# 457_I2S_Stereo_Sound_Speaker_Rev020001.net
KiCad netlist of a schematic drawn in EAGLE
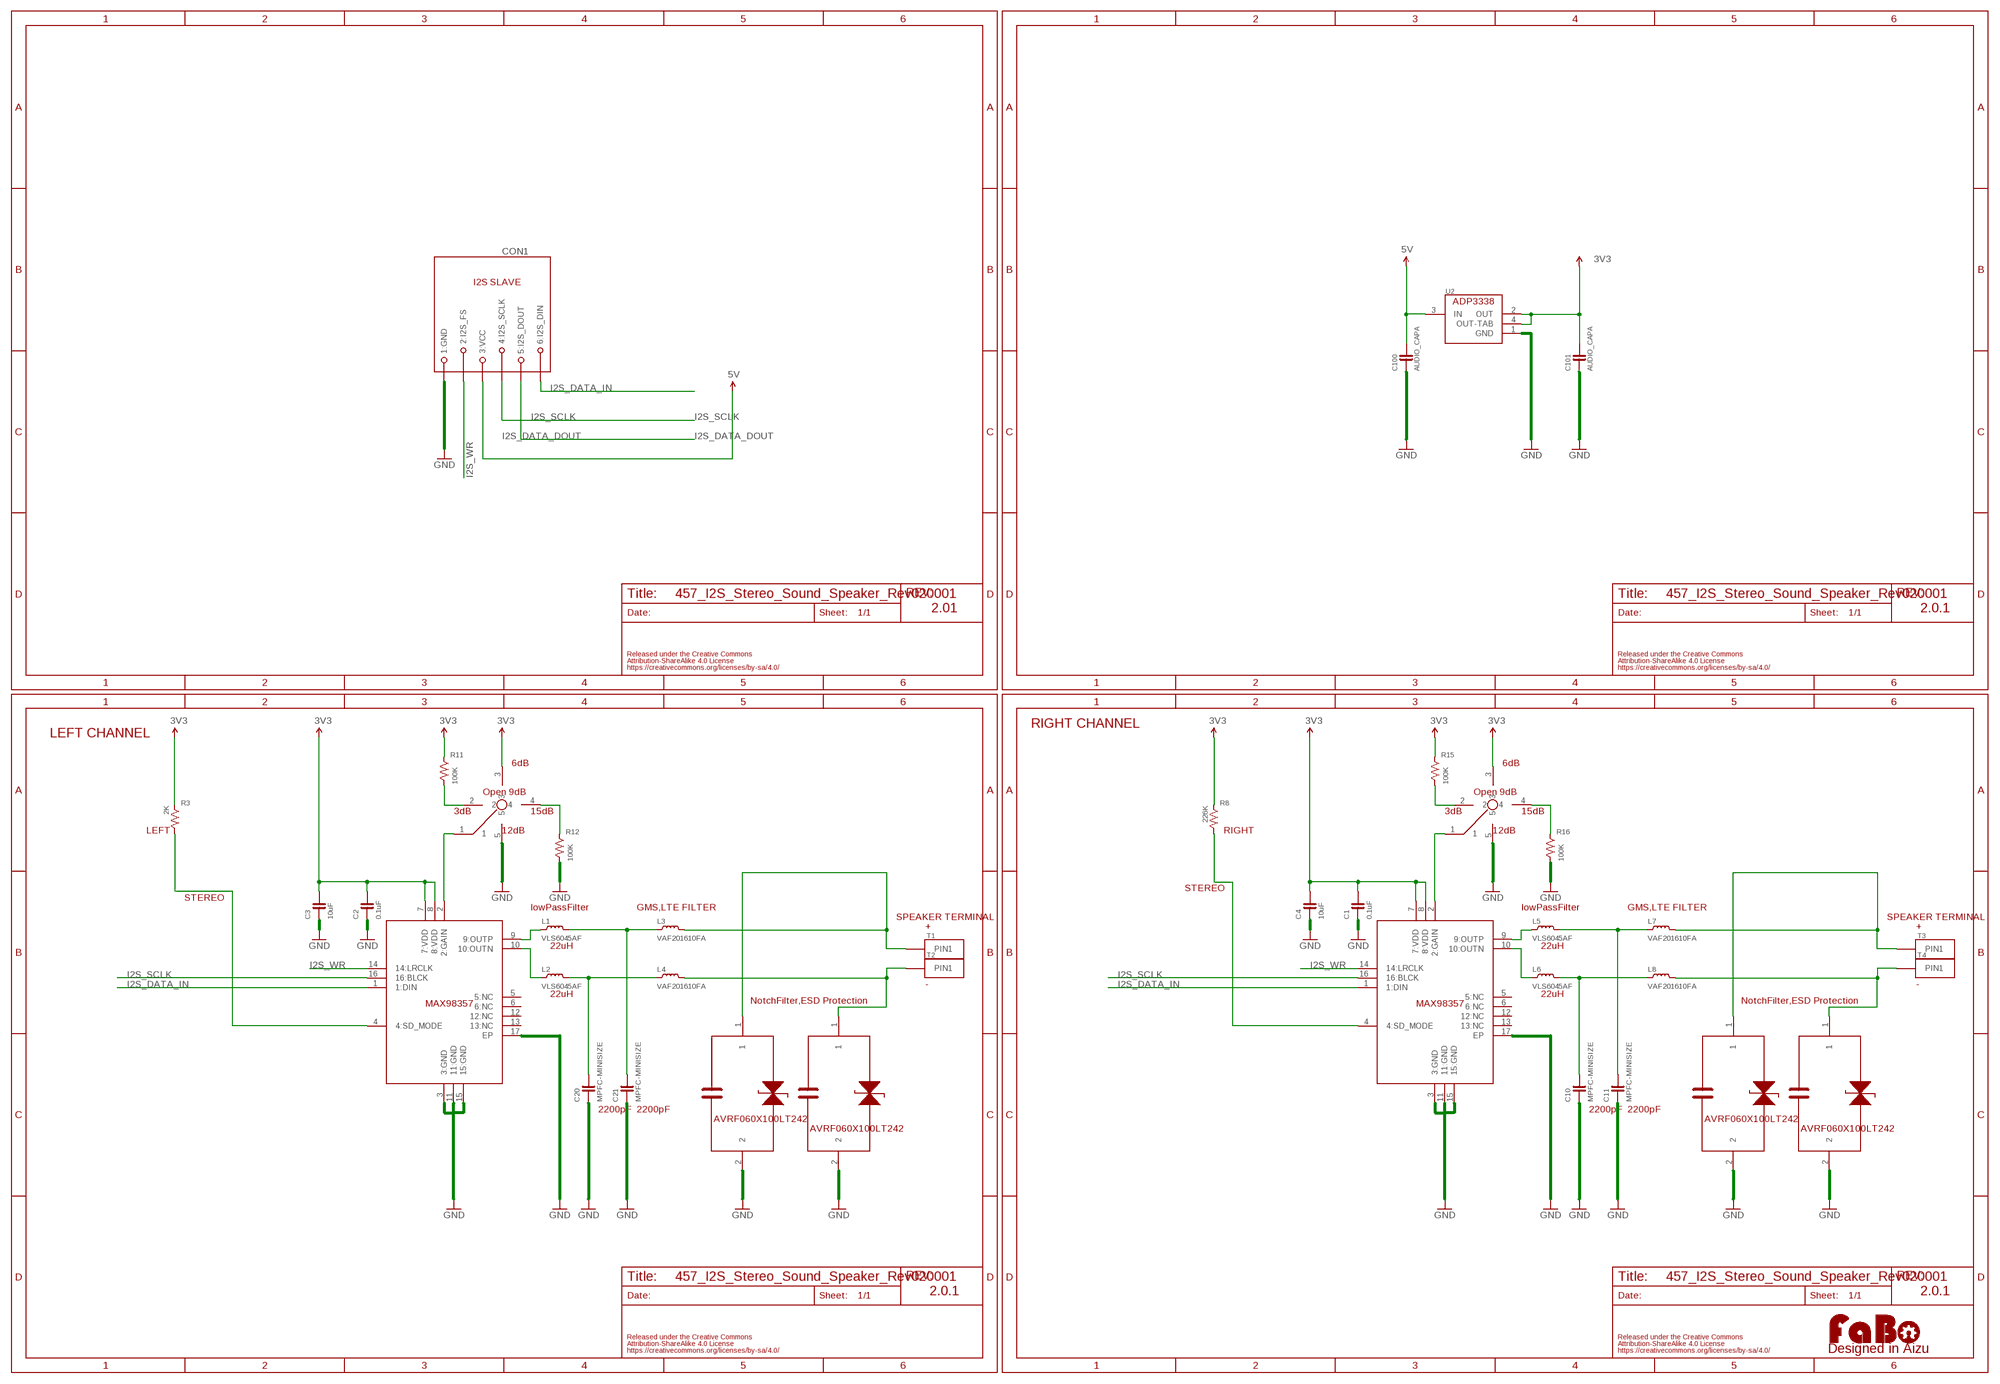
[diagram p0: schematic, sheet 1]

(export (version "E")
  (design (tool "Eeschema 10.0.6"))
  (components
    (comp (ref "C1")
      (value "0.1uF")
      (footprint "eagle-import:0603")
      (libsource (lib "eagle-import") (part "CAPACITOR-0603"))
    )
    (comp (ref "C2")
      (value "0.1uF")
      (footprint "eagle-import:0603")
      (libsource (lib "eagle-import") (part "CAPACITOR-0603"))
    )
    (comp (ref "C3")
      (value "10uF")
      (footprint "eagle-import:0603")
      (libsource (lib "eagle-import") (part "CAPACITOR-0603"))
    )
    (comp (ref "C4")
      (value "10uF")
      (footprint "eagle-import:0603")
      (libsource (lib "eagle-import") (part "CAPACITOR-0603"))
    )
    (comp (ref "C10")
      (value "MPFC-MINISIZE")
      (footprint "eagle-import:DIP-MPFC")
      (libsource (lib "eagle-import") (part "MPFC-MINISIZE"))
    )
    (comp (ref "C11")
      (value "MPFC-MINISIZE")
      (footprint "eagle-import:DIP-MPFC")
      (libsource (lib "eagle-import") (part "MPFC-MINISIZE"))
    )
    (comp (ref "C20")
      (value "MPFC-MINISIZE")
      (footprint "eagle-import:DIP-MPFC")
      (libsource (lib "eagle-import") (part "MPFC-MINISIZE"))
    )
    (comp (ref "C21")
      (value "MPFC-MINISIZE")
      (footprint "eagle-import:DIP-MPFC")
      (libsource (lib "eagle-import") (part "MPFC-MINISIZE"))
    )
    (comp (ref "C100")
      (value "AUDIO_CAPA")
      (footprint "eagle-import:3216")
      (libsource (lib "eagle-import") (part "AUDIO_CAPA"))
    )
    (comp (ref "C101")
      (value "AUDIO_CAPA")
      (footprint "eagle-import:3216")
      (libsource (lib "eagle-import") (part "AUDIO_CAPA"))
    )
    (comp (ref "CON1")
      (value "MODULAR-JACK-6P-RJ11_I2S_SLAVE")
      (footprint "eagle-import:7002-6PXC-X")
      (libsource (lib "eagle-import") (part "MODULAR-JACK-6P-RJ11_I2S_SLAVE"))
    )
    (comp (ref "L1")
      (value "VLS6045AF")
      (footprint "eagle-import:VLS6045AF")
      (libsource (lib "eagle-import") (part "VLS6045AF"))
    )
    (comp (ref "L2")
      (value "VLS6045AF")
      (footprint "eagle-import:VLS6045AF")
      (libsource (lib "eagle-import") (part "VLS6045AF"))
    )
    (comp (ref "L3")
      (value "VAF201610FA")
      (footprint "eagle-import:VAF201610FA-1")
      (libsource (lib "eagle-import") (part "VAF201610FA"))
    )
    (comp (ref "L4")
      (value "VAF201610FA")
      (footprint "eagle-import:VAF201610FA-1")
      (libsource (lib "eagle-import") (part "VAF201610FA"))
    )
    (comp (ref "L5")
      (value "VLS6045AF")
      (footprint "eagle-import:VLS6045AF")
      (libsource (lib "eagle-import") (part "VLS6045AF"))
    )
    (comp (ref "L6")
      (value "VLS6045AF")
      (footprint "eagle-import:VLS6045AF")
      (libsource (lib "eagle-import") (part "VLS6045AF"))
    )
    (comp (ref "L7")
      (value "VAF201610FA")
      (footprint "eagle-import:VAF201610FA-1")
      (libsource (lib "eagle-import") (part "VAF201610FA"))
    )
    (comp (ref "L8")
      (value "VAF201610FA")
      (footprint "eagle-import:VAF201610FA-1")
      (libsource (lib "eagle-import") (part "VAF201610FA"))
    )
    (comp (ref "LEFTAMP")
      (value "MAX98357A,B")
      (footprint "eagle-import:TQFN(16L3_3_0.75)")
      (libsource (lib "eagle-import") (part "MAX98357A,B"))
    )
    (comp (ref "LOGO1")
      (value "LOGO_FABO-M")
      (footprint "eagle-import:LOGO_FABO_M")
      (libsource (lib "eagle-import") (part "LOGO_FABO-M"))
    )
    (comp (ref "R3")
      (value "2K")
      (footprint "eagle-import:0603")
      (libsource (lib "eagle-import") (part "RESISTOR-0603"))
    )
    (comp (ref "R8")
      (value "226K")
      (footprint "eagle-import:0603")
      (libsource (lib "eagle-import") (part "RESISTOR-0603"))
    )
    (comp (ref "R11")
      (value "100K")
      (footprint "eagle-import:0603")
      (libsource (lib "eagle-import") (part "RESISTOR-0603"))
    )
    (comp (ref "R12")
      (value "100K")
      (footprint "eagle-import:0603")
      (libsource (lib "eagle-import") (part "RESISTOR-0603"))
    )
    (comp (ref "R15")
      (value "100K")
      (footprint "eagle-import:0603")
      (libsource (lib "eagle-import") (part "RESISTOR-0603"))
    )
    (comp (ref "R16")
      (value "100K")
      (footprint "eagle-import:0603")
      (libsource (lib "eagle-import") (part "RESISTOR-0603"))
    )
    (comp (ref "RIGHTAMP")
      (value "MAX98357A,B")
      (footprint "eagle-import:TQFN(16L3_3_0.75)")
      (libsource (lib "eagle-import") (part "MAX98357A,B"))
    )
    (comp (ref "T1")
      (value "TBL004-508")
      (footprint "eagle-import:TBL004-508")
      (libsource (lib "eagle-import") (part "TBL004-508"))
    )
    (comp (ref "T2")
      (value "TBL004-508")
      (footprint "eagle-import:TBL004-508")
      (libsource (lib "eagle-import") (part "TBL004-508"))
    )
    (comp (ref "T3")
      (value "TBL004-508")
      (footprint "eagle-import:TBL004-508")
      (libsource (lib "eagle-import") (part "TBL004-508"))
    )
    (comp (ref "T4")
      (value "TBL004-508")
      (footprint "eagle-import:TBL004-508")
      (libsource (lib "eagle-import") (part "TBL004-508"))
    )
    (comp (ref "U$5")
      (value "AVRF060X100LT242")
      (footprint "eagle-import:AVRF0X0X100LT_0603")
      (libsource (lib "eagle-import") (part "AVRF060X100LT242"))
    )
    (comp (ref "U$7")
      (value "AVRF060X100LT242")
      (footprint "eagle-import:AVRF0X0X100LT_0603")
      (libsource (lib "eagle-import") (part "AVRF060X100LT242"))
    )
    (comp (ref "U$9")
      (value "AVRF060X100LT242")
      (footprint "eagle-import:AVRF0X0X100LT_0603")
      (libsource (lib "eagle-import") (part "AVRF060X100LT242"))
    )
    (comp (ref "U$11")
      (value "AVRF060X100LT242")
      (footprint "eagle-import:AVRF0X0X100LT_0603")
      (libsource (lib "eagle-import") (part "AVRF060X100LT242"))
    )
    (comp (ref "U$13")
      (value "2MMJUMPER_CROSS")
      (footprint "eagle-import:PINHEAD2MM_CROSS")
      (libsource (lib "eagle-import") (part "2MMJUMPER_CROSS"))
    )
    (comp (ref "U$14")
      (value "2MMJUMPER_CROSS")
      (footprint "eagle-import:PINHEAD2MM_CROSS")
      (libsource (lib "eagle-import") (part "2MMJUMPER_CROSS"))
    )
    (comp (ref "U2")
      (value "ADP3338AKCZ")
      (footprint "eagle-import:SOT-223-KC3")
      (libsource (lib "eagle-import") (part "ADP3338AKCZ"))
    )
  )
  (nets
    (net (code "1") (name "/I2S_DATA_DOUT") (class "Default")
      (node (ref "CON1") (pin "5") (pinfunction "5:I2S_DOUT_5") (pintype "output"))
    )
    (net (code "2") (name "/I2S_DATA_IN") (class "Default")
      (node (ref "CON1") (pin "6") (pinfunction "6:I2S_DIN_6") (pintype "input"))
      (node (ref "LEFTAMP") (pin "1") (pinfunction "1:DIN_1") (pintype "bidirectional"))
      (node (ref "RIGHTAMP") (pin "1") (pinfunction "1:DIN_1") (pintype "bidirectional"))
    )
    (net (code "3") (name "/I2S_SCLK") (class "Default")
      (node (ref "CON1") (pin "4") (pinfunction "4:I2S_SCLK_4") (pintype "bidirectional"))
      (node (ref "LEFTAMP") (pin "16") (pinfunction "16:BLCK_16") (pintype "bidirectional"))
      (node (ref "RIGHTAMP") (pin "16") (pinfunction "16:BLCK_16") (pintype "bidirectional"))
    )
    (net (code "4") (name "/I2S_WR") (class "Default")
      (node (ref "CON1") (pin "2") (pinfunction "2:I2S_FS_2") (pintype "bidirectional"))
      (node (ref "LEFTAMP") (pin "14") (pinfunction "14:LRCLK_14") (pintype "bidirectional"))
      (node (ref "RIGHTAMP") (pin "14") (pinfunction "14:LRCLK_14") (pintype "bidirectional"))
    )
    (net (code "5") (name "3V3") (class "Default")
      (node (ref "C1") (pin "2") (pinfunction "2_2") (pintype "passive"))
      (node (ref "C101") (pin "2") (pinfunction "2_2") (pintype "passive"))
      (node (ref "C2") (pin "2") (pinfunction "2_2") (pintype "passive"))
      (node (ref "C3") (pin "2") (pinfunction "2_2") (pintype "passive"))
      (node (ref "C4") (pin "2") (pinfunction "2_2") (pintype "passive"))
      (node (ref "LEFTAMP") (pin "7") (pinfunction "7:VDD_7") (pintype "bidirectional"))
      (node (ref "LEFTAMP") (pin "8") (pinfunction "8:VDD_8") (pintype "bidirectional"))
      (node (ref "R11") (pin "1") (pinfunction "1_1") (pintype "bidirectional"))
      (node (ref "R15") (pin "1") (pinfunction "1_1") (pintype "bidirectional"))
      (node (ref "R3") (pin "1") (pinfunction "1_1") (pintype "bidirectional"))
      (node (ref "R8") (pin "1") (pinfunction "1_1") (pintype "bidirectional"))
      (node (ref "RIGHTAMP") (pin "7") (pinfunction "7:VDD_7") (pintype "bidirectional"))
      (node (ref "RIGHTAMP") (pin "8") (pinfunction "8:VDD_8") (pintype "bidirectional"))
      (node (ref "U$13") (pin "3") (pinfunction "3_3") (pintype "bidirectional"))
      (node (ref "U$14") (pin "3") (pinfunction "3_3") (pintype "bidirectional"))
      (node (ref "U2") (pin "2") (pinfunction "OUT_2") (pintype "bidirectional"))
      (node (ref "U2") (pin "4") (pinfunction "OUT-TAB_4") (pintype "bidirectional"))
    )
    (net (code "6") (name "5V") (class "Default")
      (node (ref "C100") (pin "2") (pinfunction "2_2") (pintype "passive"))
      (node (ref "CON1") (pin "3") (pinfunction "3:VCC_3") (pintype "power_in"))
      (node (ref "U2") (pin "3") (pinfunction "IN_3") (pintype "bidirectional"))
    )
    (net (code "7") (name "GND") (class "Default")
      (node (ref "C1") (pin "1") (pinfunction "1_1") (pintype "passive"))
      (node (ref "C10") (pin "1") (pinfunction "1_1") (pintype "passive"))
      (node (ref "C100") (pin "1") (pinfunction "1_1") (pintype "passive"))
      (node (ref "C101") (pin "1") (pinfunction "1_1") (pintype "passive"))
      (node (ref "C11") (pin "1") (pinfunction "1_1") (pintype "passive"))
      (node (ref "C2") (pin "1") (pinfunction "1_1") (pintype "passive"))
      (node (ref "C20") (pin "1") (pinfunction "1_1") (pintype "passive"))
      (node (ref "C21") (pin "1") (pinfunction "1_1") (pintype "passive"))
      (node (ref "C3") (pin "1") (pinfunction "1_1") (pintype "passive"))
      (node (ref "C4") (pin "1") (pinfunction "1_1") (pintype "passive"))
      (node (ref "CON1") (pin "1") (pinfunction "1:GND_1") (pintype "power_in"))
      (node (ref "LEFTAMP") (pin "11") (pinfunction "11:GND_11") (pintype "bidirectional"))
      (node (ref "LEFTAMP") (pin "15") (pinfunction "15:GND_15") (pintype "bidirectional"))
      (node (ref "LEFTAMP") (pin "17") (pinfunction "EP_17") (pintype "bidirectional"))
      (node (ref "LEFTAMP") (pin "3") (pinfunction "3:GND_3") (pintype "bidirectional"))
      (node (ref "R12") (pin "2") (pinfunction "2_2") (pintype "bidirectional"))
      (node (ref "R16") (pin "2") (pinfunction "2_2") (pintype "bidirectional"))
      (node (ref "RIGHTAMP") (pin "11") (pinfunction "11:GND_11") (pintype "bidirectional"))
      (node (ref "RIGHTAMP") (pin "15") (pinfunction "15:GND_15") (pintype "bidirectional"))
      (node (ref "RIGHTAMP") (pin "17") (pinfunction "EP_17") (pintype "bidirectional"))
      (node (ref "RIGHTAMP") (pin "3") (pinfunction "3:GND_3") (pintype "bidirectional"))
      (node (ref "U$11") (pin "2") (pinfunction "2_2") (pintype "bidirectional"))
      (node (ref "U$13") (pin "5") (pinfunction "5_5") (pintype "bidirectional"))
      (node (ref "U$14") (pin "5") (pinfunction "5_5") (pintype "bidirectional"))
      (node (ref "U$5") (pin "2") (pinfunction "2_2") (pintype "bidirectional"))
      (node (ref "U$7") (pin "2") (pinfunction "2_2") (pintype "bidirectional"))
      (node (ref "U$9") (pin "2") (pinfunction "2_2") (pintype "bidirectional"))
      (node (ref "U2") (pin "1") (pinfunction "GND_1") (pintype "bidirectional"))
    )
    (net (code "8") (name "Net-(C10-Pad2)") (class "Default")
      (node (ref "C10") (pin "2") (pinfunction "2_2") (pintype "passive"))
      (node (ref "L6") (pin "2") (pinfunction "2_2") (pintype "bidirectional"))
      (node (ref "L8") (pin "1") (pinfunction "1_1") (pintype "bidirectional"))
    )
    (net (code "9") (name "Net-(C11-Pad2)") (class "Default")
      (node (ref "C11") (pin "2") (pinfunction "2_2") (pintype "passive"))
      (node (ref "L5") (pin "2") (pinfunction "2_2") (pintype "bidirectional"))
      (node (ref "L7") (pin "1") (pinfunction "1_1") (pintype "bidirectional"))
    )
    (net (code "10") (name "Net-(C20-Pad2)") (class "Default")
      (node (ref "C20") (pin "2") (pinfunction "2_2") (pintype "passive"))
      (node (ref "L2") (pin "2") (pinfunction "2_2") (pintype "bidirectional"))
      (node (ref "L4") (pin "1") (pinfunction "1_1") (pintype "bidirectional"))
    )
    (net (code "11") (name "Net-(C21-Pad2)") (class "Default")
      (node (ref "C21") (pin "2") (pinfunction "2_2") (pintype "passive"))
      (node (ref "L1") (pin "2") (pinfunction "2_2") (pintype "bidirectional"))
      (node (ref "L3") (pin "1") (pinfunction "1_1") (pintype "bidirectional"))
    )
    (net (code "12") (name "Net-(L3-Pad2)") (class "Default")
      (node (ref "L3") (pin "2") (pinfunction "2_2") (pintype "bidirectional"))
      (node (ref "T1") (pin "P$1") (pinfunction "PIN1_P$1") (pintype "bidirectional"))
      (node (ref "T1") (pin "P$2") (pinfunction "PIN1_P$2") (pintype "bidirectional"))
      (node (ref "U$9") (pin "1") (pinfunction "1_1") (pintype "bidirectional"))
    )
    (net (code "13") (name "Net-(L4-Pad2)") (class "Default")
      (node (ref "L4") (pin "2") (pinfunction "2_2") (pintype "bidirectional"))
      (node (ref "T2") (pin "P$1") (pinfunction "PIN1_P$1") (pintype "bidirectional"))
      (node (ref "T2") (pin "P$2") (pinfunction "PIN1_P$2") (pintype "bidirectional"))
      (node (ref "U$11") (pin "1") (pinfunction "1_1") (pintype "bidirectional"))
    )
    (net (code "14") (name "Net-(L7-Pad2)") (class "Default")
      (node (ref "L7") (pin "2") (pinfunction "2_2") (pintype "bidirectional"))
      (node (ref "T3") (pin "P$1") (pinfunction "PIN1_P$1") (pintype "bidirectional"))
      (node (ref "T3") (pin "P$2") (pinfunction "PIN1_P$2") (pintype "bidirectional"))
      (node (ref "U$5") (pin "1") (pinfunction "1_1") (pintype "bidirectional"))
    )
    (net (code "15") (name "Net-(L8-Pad2)") (class "Default")
      (node (ref "L8") (pin "2") (pinfunction "2_2") (pintype "bidirectional"))
      (node (ref "T4") (pin "P$1") (pinfunction "PIN1_P$1") (pintype "bidirectional"))
      (node (ref "T4") (pin "P$2") (pinfunction "PIN1_P$2") (pintype "bidirectional"))
      (node (ref "U$7") (pin "1") (pinfunction "1_1") (pintype "bidirectional"))
    )
    (net (code "16") (name "Net-(LEFTAMP-2:GAIN)") (class "Default")
      (node (ref "LEFTAMP") (pin "2") (pinfunction "2:GAIN_2") (pintype "bidirectional"))
      (node (ref "U$13") (pin "1") (pinfunction "1_1") (pintype "bidirectional"))
    )
    (net (code "17") (name "Net-(LEFTAMP-4:SD_MODE)") (class "Default")
      (node (ref "LEFTAMP") (pin "4") (pinfunction "4:SD_MODE_4") (pintype "bidirectional"))
      (node (ref "R3") (pin "2") (pinfunction "2_2") (pintype "bidirectional"))
    )
    (net (code "18") (name "Net-(LEFTAMP-9:OUTP)") (class "Default")
      (node (ref "L1") (pin "1") (pinfunction "1_1") (pintype "bidirectional"))
      (node (ref "LEFTAMP") (pin "9") (pinfunction "9:OUTP_9") (pintype "bidirectional"))
    )
    (net (code "19") (name "Net-(LEFTAMP-10:OUTN)") (class "Default")
      (node (ref "L2") (pin "1") (pinfunction "1_1") (pintype "bidirectional"))
      (node (ref "LEFTAMP") (pin "10") (pinfunction "10:OUTN_10") (pintype "bidirectional"))
    )
    (net (code "20") (name "Net-(R11-Pad2)") (class "Default")
      (node (ref "R11") (pin "2") (pinfunction "2_2") (pintype "bidirectional"))
      (node (ref "U$13") (pin "2") (pinfunction "2_2") (pintype "bidirectional"))
    )
    (net (code "21") (name "Net-(R12-Pad1)") (class "Default")
      (node (ref "R12") (pin "1") (pinfunction "1_1") (pintype "bidirectional"))
      (node (ref "U$13") (pin "4") (pinfunction "4_4") (pintype "bidirectional"))
    )
    (net (code "22") (name "Net-(R15-Pad2)") (class "Default")
      (node (ref "R15") (pin "2") (pinfunction "2_2") (pintype "bidirectional"))
      (node (ref "U$14") (pin "2") (pinfunction "2_2") (pintype "bidirectional"))
    )
    (net (code "23") (name "Net-(R16-Pad1)") (class "Default")
      (node (ref "R16") (pin "1") (pinfunction "1_1") (pintype "bidirectional"))
      (node (ref "U$14") (pin "4") (pinfunction "4_4") (pintype "bidirectional"))
    )
    (net (code "24") (name "Net-(RIGHTAMP-2:GAIN)") (class "Default")
      (node (ref "RIGHTAMP") (pin "2") (pinfunction "2:GAIN_2") (pintype "bidirectional"))
      (node (ref "U$14") (pin "1") (pinfunction "1_1") (pintype "bidirectional"))
    )
    (net (code "25") (name "Net-(RIGHTAMP-4:SD_MODE)") (class "Default")
      (node (ref "R8") (pin "2") (pinfunction "2_2") (pintype "bidirectional"))
      (node (ref "RIGHTAMP") (pin "4") (pinfunction "4:SD_MODE_4") (pintype "bidirectional"))
    )
    (net (code "26") (name "Net-(RIGHTAMP-9:OUTP)") (class "Default")
      (node (ref "L5") (pin "1") (pinfunction "1_1") (pintype "bidirectional"))
      (node (ref "RIGHTAMP") (pin "9") (pinfunction "9:OUTP_9") (pintype "bidirectional"))
    )
    (net (code "27") (name "Net-(RIGHTAMP-10:OUTN)") (class "Default")
      (node (ref "L6") (pin "1") (pinfunction "1_1") (pintype "bidirectional"))
      (node (ref "RIGHTAMP") (pin "10") (pinfunction "10:OUTN_10") (pintype "bidirectional"))
    )
    (net (code "28") (name "unconnected-(LEFTAMP-5:NC-Pad5)") (class "Default")
      (node (ref "LEFTAMP") (pin "5") (pinfunction "5:NC_5") (pintype "no_connect"))
    )
    (net (code "29") (name "unconnected-(LEFTAMP-6:NC-Pad6)") (class "Default")
      (node (ref "LEFTAMP") (pin "6") (pinfunction "6:NC_6") (pintype "no_connect"))
    )
    (net (code "30") (name "unconnected-(LEFTAMP-12:NC-Pad12)") (class "Default")
      (node (ref "LEFTAMP") (pin "12") (pinfunction "12:NC_12") (pintype "no_connect"))
    )
    (net (code "31") (name "unconnected-(LEFTAMP-13:NC-Pad13)") (class "Default")
      (node (ref "LEFTAMP") (pin "13") (pinfunction "13:NC_13") (pintype "no_connect"))
    )
    (net (code "32") (name "unconnected-(RIGHTAMP-5:NC-Pad5)") (class "Default")
      (node (ref "RIGHTAMP") (pin "5") (pinfunction "5:NC_5") (pintype "no_connect"))
    )
    (net (code "33") (name "unconnected-(RIGHTAMP-6:NC-Pad6)") (class "Default")
      (node (ref "RIGHTAMP") (pin "6") (pinfunction "6:NC_6") (pintype "no_connect"))
    )
    (net (code "34") (name "unconnected-(RIGHTAMP-12:NC-Pad12)") (class "Default")
      (node (ref "RIGHTAMP") (pin "12") (pinfunction "12:NC_12") (pintype "no_connect"))
    )
    (net (code "35") (name "unconnected-(RIGHTAMP-13:NC-Pad13)") (class "Default")
      (node (ref "RIGHTAMP") (pin "13") (pinfunction "13:NC_13") (pintype "no_connect"))
    )
  )
)
